# Battery_Charger.net
KiCad netlist of a schematic drawn in Altium Designer
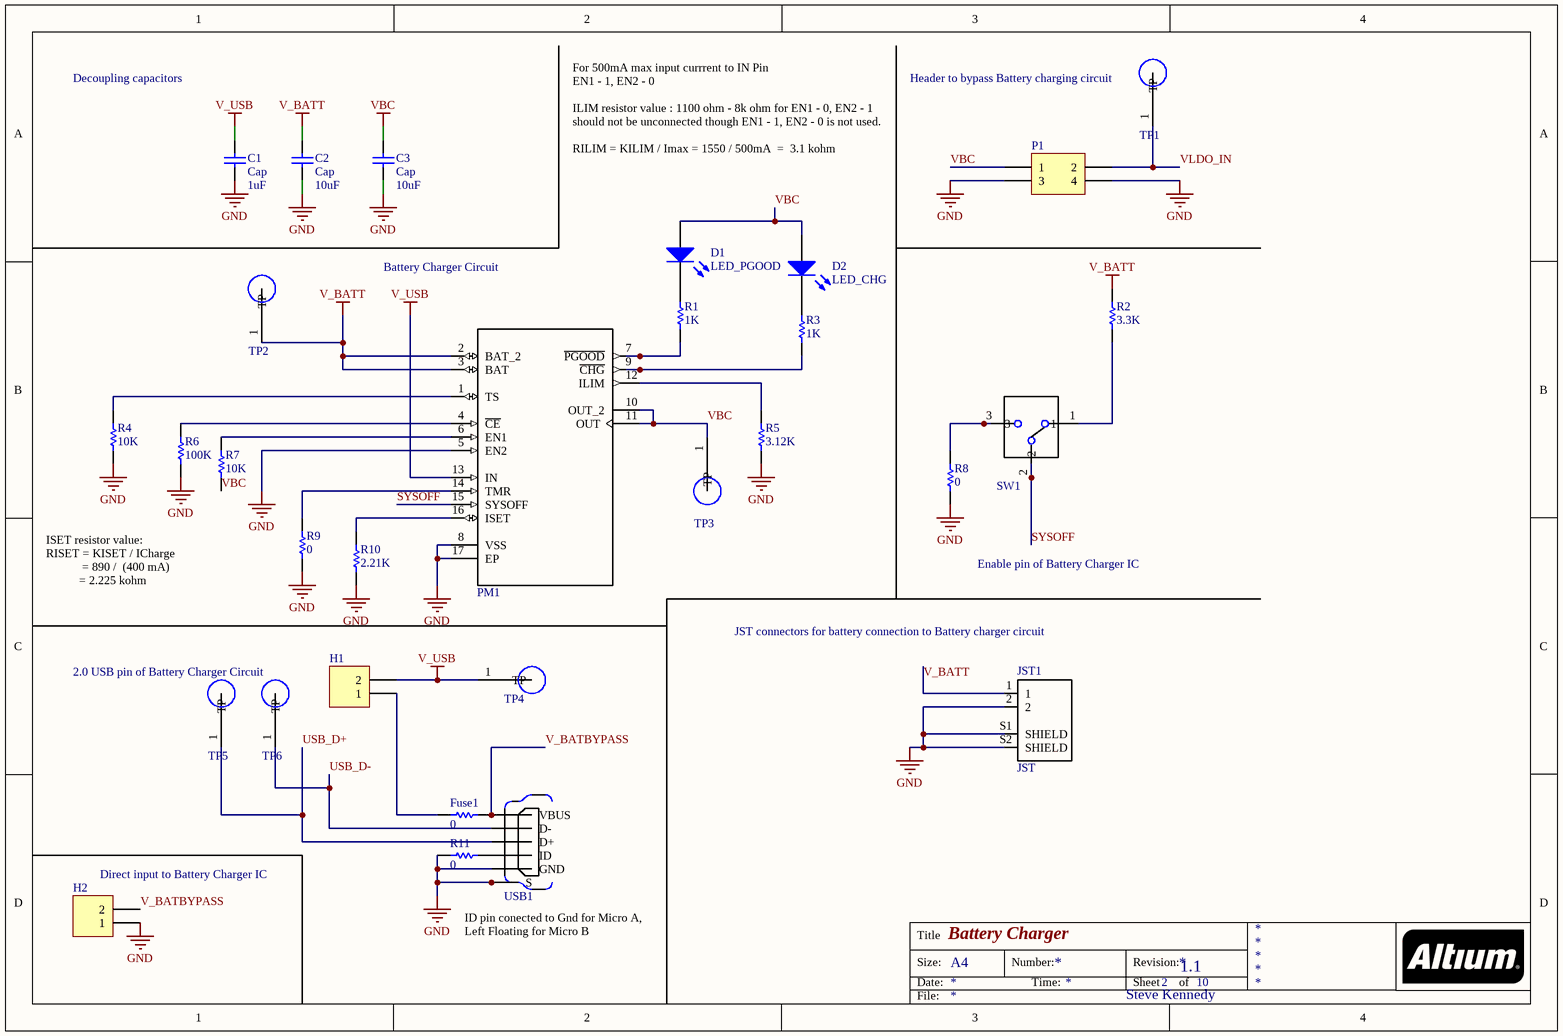
[diagram p0: Battery_Charger.SchDoc]

(export (version "E")
  (design (tool "Eeschema 10.0.6"))
  (components
    (comp (ref "C1")
      (value "Cap")
      (footprint "1608[0603]")
      (description "10000pF ±10% 50V Ceramic Capacitor X7R 0603 (1608 Metric)")
      (fields
        (field (name "ALTIUM_VALUE") "1uF")
        (field (name "DIGI-KEY PART NUMBER") "1276-1009-1-ND")
        (field (name "MANUFACTURER") "Samsung Electro-Mechanics")
      )
      (libsource (lib "Miscellaneous Devices") (part "Cap"))
    )
    (comp (ref "C2")
      (value "Cap")
      (footprint "1608[0603]")
      (description "10000pF ±10% 50V Ceramic Capacitor X7R 0603 (1608 Metric)")
      (fields
        (field (name "ALTIUM_VALUE") "10uF")
        (field (name "DIGI-KEY PART NUMBER") "1276-1009-1-ND")
        (field (name "MANUFACTURER") "Samsung Electro-Mechanics")
      )
      (libsource (lib "Miscellaneous Devices") (part "Cap"))
    )
    (comp (ref "C3")
      (value "Cap")
      (footprint "1608[0603]")
      (description "10000pF ±10% 50V Ceramic Capacitor X7R 0603 (1608 Metric)")
      (fields
        (field (name "ALTIUM_VALUE") "10uF")
        (field (name "DIGI-KEY PART NUMBER") "1276-1009-1-ND")
        (field (name "MANUFACTURER") "Samsung Electro-Mechanics")
      )
      (libsource (lib "Miscellaneous Devices") (part "Cap"))
    )
    (comp (ref "D1")
      (value "LED_PGOOD")
      (footprint "1608[0603]")
      (description "LED GREEN DIFFUSED 0603 SMD")
      (fields
        (field (name "DIGI-KEY PART NUMBER") "475-3118-1-ND")
        (field (name "MANUFACTURER") "OSRAM Opto Semiconductors Inc.")
      )
      (libsource (lib "Miscellaneous Devices") (part "LED2"))
    )
    (comp (ref "D2")
      (value "LED_CHG")
      (footprint "1608[0603]")
      (description "Blue 470nm LED Indication - Discrete 2.85V 0603 (1608 Metric)")
      (fields
        (field (name "DIGI-KEY PART NUMBER") "475-2816-1-ND")
        (field (name "MANUFACTURER") "OSRAM Opto Semiconductors Inc.")
      )
      (libsource (lib "Miscellaneous Devices") (part "LED2"))
    )
    (comp (ref "Fuse1")
      (value "0")
      (footprint "1608[0603]")
      (fields
        (field (name "DIGI-KEY PART NUMBER") "RNCP0603FTD10K0CT-ND")
        (field (name "MANUFACTURER") "Stackpole Electronics Inc")
        (field (name "MANUFACTURER PART NUMBER") "RNCP0603FTD10K0")
      )
      (libsource (lib "Miscellaneous Devices") (part "Res1"))
    )
    (comp (ref "H1")
      (value "Header 2")
      (footprint "HDR1X2")
      (description "CONN HEADER VERT 8POS 2.54MM")
      (fields
        (field (name "DIGI-KEY PART NUMBER") "A121467-ND")
        (field (name "MANUFACTURER") "TE Connectivity AMP Connectors")
      )
      (libsource (lib "Miscellaneous Connectors") (part "Header 2"))
    )
    (comp (ref "H2")
      (value "Header 2")
      (footprint "HDR1X2")
      (description "CONN HEADER VERT 8POS 2.54MM")
      (fields
        (field (name "DIGI-KEY PART NUMBER") "A121467-ND")
        (field (name "MANUFACTURER") "TE Connectivity AMP Connectors")
      )
      (libsource (lib "Miscellaneous Connectors") (part "Header 2"))
    )
    (comp (ref "JST1")
      (value "JST")
      (footprint "JST")
      (description "SWITCH SLIDE SPDT 200MA 12V")
      (fields
        (field (name "DIGI-KEY PART NUMBER") "563-1318-1-ND")
        (field (name "MANUFACTURER") "Nidec Copal Electronics")
      )
      (libsource (lib "JST_header") (part "JST"))
    )
    (comp (ref "P1")
      (value "Header 2X2H")
      (footprint "HDR2X2H")
      (description "CONN HEADER VERT 8POS 2.54MM")
      (fields
        (field (name "DIGI-KEY PART NUMBER") "A121467-ND")
        (field (name "MANUFACTURER") "TE Connectivity AMP Connectors")
      )
      (libsource (lib "Miscellaneous Connectors") (part "Header 2X2H"))
    )
    (comp (ref "PM1")
      (value "POWER_IC")
      (footprint "Power_management")
      (description "IC LI-ION CHARGE MGMT 16-QFN")
      (fields
        (field (name "MANUFACTURER") "Texas Instruments")
        (field (name "DIGI-KEY PART NUMBER") "296-38874-1-ND")
      )
      (libsource (lib "Power_management_chip") (part "POWER_IC"))
    )
    (comp (ref "R1")
      (value "1K")
      (footprint "1608[0603]")
      (fields
        (field (name "DIGI-KEY PART NUMBER") "RNCP0603FTD10K0CT-ND")
        (field (name "MANUFACTURER") "Stackpole Electronics Inc")
        (field (name "MANUFACTURER PART NUMBER") "RNCP0603FTD10K0")
      )
      (libsource (lib "Miscellaneous Devices") (part "Res1"))
    )
    (comp (ref "R2")
      (value "3.3K")
      (footprint "1608[0603]")
      (fields
        (field (name "DIGI-KEY PART NUMBER") "RNCP0603FTD10K0CT-ND")
        (field (name "MANUFACTURER") "Stackpole Electronics Inc")
        (field (name "MANUFACTURER PART NUMBER") "RNCP0603FTD10K0")
      )
      (libsource (lib "Miscellaneous Devices") (part "Res1"))
    )
    (comp (ref "R3")
      (value "1K")
      (footprint "1608[0603]")
      (fields
        (field (name "DIGI-KEY PART NUMBER") "RNCP0603FTD10K0CT-ND")
        (field (name "MANUFACTURER") "Stackpole Electronics Inc")
        (field (name "MANUFACTURER PART NUMBER") "RNCP0603FTD10K0")
      )
      (libsource (lib "Miscellaneous Devices") (part "Res1"))
    )
    (comp (ref "R4")
      (value "10K")
      (footprint "1608[0603]")
      (fields
        (field (name "DIGI-KEY PART NUMBER") "RNCP0603FTD10K0CT-ND")
        (field (name "MANUFACTURER") "Stackpole Electronics Inc")
        (field (name "MANUFACTURER PART NUMBER") "RNCP0603FTD10K0")
      )
      (libsource (lib "Miscellaneous Devices") (part "Res1"))
    )
    (comp (ref "R5")
      (value "3.12K")
      (footprint "1608[0603]")
      (fields
        (field (name "DIGI-KEY PART NUMBER") "311-2562-1-ND")
        (field (name "MANUFACTURER") "Yageo")
        (field (name "MANUFACTURER PART NUMBER") "RT0603DRE073K12L")
      )
      (libsource (lib "Miscellaneous Devices") (part "Res1"))
    )
    (comp (ref "R6")
      (value "100K")
      (footprint "1608[0603]")
      (fields
        (field (name "DIGI-KEY PART NUMBER") "RNCP0603FTD10K0CT-ND")
        (field (name "MANUFACTURER") "Stackpole Electronics Inc")
        (field (name "MANUFACTURER PART NUMBER") "RNCP0603FTD10K0")
      )
      (libsource (lib "Miscellaneous Devices") (part "Res1"))
    )
    (comp (ref "R7")
      (value "10K")
      (footprint "1608[0603]")
      (fields
        (field (name "DIGI-KEY PART NUMBER") "RNCP0603FTD10K0CT-ND")
        (field (name "MANUFACTURER") "Stackpole Electronics Inc")
        (field (name "MANUFACTURER PART NUMBER") "RNCP0603FTD10K0")
      )
      (libsource (lib "Miscellaneous Devices") (part "Res1"))
    )
    (comp (ref "R8")
      (value "0")
      (footprint "1608[0603]")
      (description "RES SMD 0 OHM JUMPER 1/10W 0603")
      (fields (field (name "DIGI-KEY PART NUMBER") "311-0.0GRCT-ND") (field (name "MANUFACTURER") "Yageo"))
      (libsource (lib "Miscellaneous Devices") (part "Res1"))
    )
    (comp (ref "R9")
      (value "0")
      (footprint "1608[0603]")
      (description "RES SMD 0 OHM JUMPER 1/10W 0603")
      (fields (field (name "DIGI-KEY PART NUMBER") "311-0.0GRCT-ND") (field (name "MANUFACTURER") "Yageo"))
      (libsource (lib "Miscellaneous Devices") (part "Res1"))
    )
    (comp (ref "R10")
      (value "2.21K")
      (footprint "1608[0603]")
      (fields
        (field (name "DIGI-KEY PART NUMBER") "P2.21KHCT-ND")
        (field (name "MANUFACTURER") "Panasonic Electronic Components")
        (field (name "MANUFACTURER PART NUMBER") "ERJ-3EKF2211V")
      )
      (libsource (lib "Miscellaneous Devices") (part "Res1"))
    )
    (comp (ref "R11")
      (value "0")
      (footprint "1608[0603]")
      (description "RES SMD 0 OHM JUMPER 1/10W 0603")
      (fields (field (name "DIGI-KEY PART NUMBER") "311-0.0GRCT-ND") (field (name "MANUFACTURER") "Yageo"))
      (libsource (lib "Miscellaneous Devices") (part "Res1"))
    )
    (comp (ref "SW1")
      (value "SW")
      (footprint "SW")
      (description "SWITCH SLIDE SPDT 200MA 12V")
      (fields
        (field (name "MANUFACTURER") "Nidec Copal Electronics")
        (field (name "DIGI-KEY PART NUMBER") "563-1318-1-ND")
      )
      (libsource (lib "Switch") (part "SW"))
    )
    (comp (ref "TP1")
      (value "TP")
      (footprint "TP")
      (description "PC TEST POINT MINIATURE")
      (fields
        (field (name "MANUFACTURER") "Keystone Electronics")
        (field (name "DIGI-KEY PART NUMBER") "36-5019CT-ND")
      )
      (libsource (lib "TP") (part "TP"))
    )
    (comp (ref "TP2")
      (value "TP")
      (footprint "TP")
      (description "PC TEST POINT MINIATURE")
      (fields
        (field (name "DIGI-KEY PART NUMBER") "36-5019CT-ND")
        (field (name "MANUFACTURER") "Keystone Electronics")
      )
      (libsource (lib "TP") (part "TP"))
    )
    (comp (ref "TP3")
      (value "TP")
      (footprint "TP")
      (description "PC TEST POINT MINIATURE")
      (fields
        (field (name "MANUFACTURER") "Keystone Electronics")
        (field (name "DIGI-KEY PART NUMBER") "36-5019CT-ND")
      )
      (libsource (lib "TP") (part "TP"))
    )
    (comp (ref "TP4")
      (value "TP")
      (footprint "TP")
      (description "PC TEST POINT MINIATURE")
      (fields
        (field (name "MANUFACTURER") "Keystone Electronics")
        (field (name "DIGI-KEY PART NUMBER") "36-5019CT-ND")
      )
      (libsource (lib "TP") (part "TP"))
    )
    (comp (ref "TP5")
      (value "TP")
      (footprint "TP")
      (description "PC TEST POINT MINIATURE")
      (fields
        (field (name "MANUFACTURER") "Keystone Electronics")
        (field (name "DIGI-KEY PART NUMBER") "36-5019CT-ND")
      )
      (libsource (lib "TP") (part "TP"))
    )
    (comp (ref "TP6")
      (value "TP")
      (footprint "TP")
      (description "PC TEST POINT MINIATURE")
      (fields
        (field (name "MANUFACTURER") "Keystone Electronics")
        (field (name "DIGI-KEY PART NUMBER") "36-5019CT-ND")
      )
      (libsource (lib "TP") (part "TP"))
    )
    (comp (ref "USB1")
      (value "USB")
      (footprint "USB")
      (description "CONN RCPT USB2.0 MICRO AB SMD RA")
      (fields
        (field (name "DIGI-KEY PART NUMBER") "609-4053-1-ND")
        (field (name "MANUFACTURER") "Amphenol ICC (FCI)")
      )
      (libsource (lib "Project_Parts") (part "USB"))
    )
  )
  (nets
    (net (code "1") (name "/SYSOFF") (class "Default")
      (node (ref "PM1") (pin "15") (pinfunction "SYSOFF_15") (pintype "input"))
      (node (ref "SW1") (pin "2") (pinfunction "2_2") (pintype "bidirectional"))
    )
    (net (code "2") (name "/USB_D+") (class "Default")
      (node (ref "TP5") (pin "1") (pinfunction "TP_1") (pintype "passive"))
      (node (ref "USB1") (pin "3") (pinfunction "D+_3") (pintype "passive"))
    )
    (net (code "3") (name "/USB_D-") (class "Default")
      (node (ref "TP6") (pin "1") (pinfunction "TP_1") (pintype "passive"))
      (node (ref "USB1") (pin "2") (pinfunction "D-_2") (pintype "passive"))
    )
    (net (code "4") (name "/VLDO_IN") (class "Default")
      (node (ref "P1") (pin "2") (pinfunction "2_2") (pintype "passive"))
      (node (ref "TP1") (pin "1") (pinfunction "TP_1") (pintype "passive"))
    )
    (net (code "5") (name "/V_BATBYPASS") (class "Default")
      (node (ref "Fuse1") (pin "1") (pinfunction "1_1") (pintype "passive"))
      (node (ref "H2") (pin "2") (pinfunction "2_2") (pintype "passive"))
      (node (ref "USB1") (pin "1") (pinfunction "VBUS_1") (pintype "power_in"))
    )
    (net (code "6") (name "GND") (class "Default")
      (node (ref "C1") (pin "1") (pinfunction "1_1") (pintype "passive"))
      (node (ref "C2") (pin "1") (pinfunction "1_1") (pintype "passive"))
      (node (ref "C3") (pin "1") (pinfunction "1_1") (pintype "passive"))
      (node (ref "H2") (pin "1") (pinfunction "1_1") (pintype "passive"))
      (node (ref "JST1") (pin "2") (pinfunction "2_2") (pintype "passive"))
      (node (ref "JST1") (pin "S1") (pinfunction "SHIELD_S1") (pintype "passive"))
      (node (ref "JST1") (pin "S2") (pinfunction "SHIELD_S2") (pintype "passive"))
      (node (ref "P1") (pin "3") (pinfunction "3_3") (pintype "passive"))
      (node (ref "P1") (pin "4") (pinfunction "4_4") (pintype "passive"))
      (node (ref "PM1") (pin "17") (pinfunction "EP_17") (pintype "passive"))
      (node (ref "PM1") (pin "5") (pinfunction "EN2_5") (pintype "input"))
      (node (ref "PM1") (pin "8") (pinfunction "VSS_8") (pintype "passive"))
      (node (ref "R10") (pin "1") (pinfunction "1_1") (pintype "passive"))
      (node (ref "R11") (pin "2") (pinfunction "2_2") (pintype "passive"))
      (node (ref "R4") (pin "1") (pinfunction "1_1") (pintype "passive"))
      (node (ref "R5") (pin "1") (pinfunction "1_1") (pintype "passive"))
      (node (ref "R6") (pin "1") (pinfunction "1_1") (pintype "passive"))
      (node (ref "R8") (pin "1") (pinfunction "1_1") (pintype "passive"))
      (node (ref "R9") (pin "1") (pinfunction "1_1") (pintype "passive"))
      (node (ref "USB1") (pin "5") (pinfunction "GND_5") (pintype "power_in"))
      (node (ref "USB1") (pin "6") (pinfunction "S_6") (pintype "power_in"))
      (node (ref "USB1") (pin "7") (pinfunction "S_7") (pintype "power_in"))
      (node (ref "USB1") (pin "8") (pinfunction "S_8") (pintype "power_in"))
      (node (ref "USB1") (pin "9") (pinfunction "S_9") (pintype "power_in"))
    )
    (net (code "7") (name "Net-(D1-K)") (class "Default")
      (node (ref "D1") (pin "2") (pinfunction "K_2") (pintype "passive"))
      (node (ref "R1") (pin "2") (pinfunction "2_2") (pintype "passive"))
    )
    (net (code "8") (name "Net-(D2-K)") (class "Default")
      (node (ref "D2") (pin "2") (pinfunction "K_2") (pintype "passive"))
      (node (ref "R3") (pin "2") (pinfunction "2_2") (pintype "passive"))
    )
    (net (code "9") (name "Net-(Fuse1-Pad2)") (class "Default")
      (node (ref "Fuse1") (pin "2") (pinfunction "2_2") (pintype "passive"))
      (node (ref "H1") (pin "1") (pinfunction "1_1") (pintype "passive"))
    )
    (net (code "10") (name "Net-(PM1-EN1)") (class "Default")
      (node (ref "PM1") (pin "6") (pinfunction "EN1_6") (pintype "input"))
      (node (ref "R7") (pin "2") (pinfunction "2_2") (pintype "passive"))
    )
    (net (code "11") (name "Net-(PM1-ILIM)") (class "Default")
      (node (ref "PM1") (pin "12") (pinfunction "ILIM_12") (pintype "output"))
      (node (ref "R5") (pin "2") (pinfunction "2_2") (pintype "passive"))
    )
    (net (code "12") (name "Net-(PM1-ISET)") (class "Default")
      (node (ref "PM1") (pin "16") (pinfunction "ISET_16") (pintype "bidirectional"))
      (node (ref "R10") (pin "2") (pinfunction "2_2") (pintype "passive"))
    )
    (net (code "13") (name "Net-(PM1-TMR)") (class "Default")
      (node (ref "PM1") (pin "14") (pinfunction "TMR_14") (pintype "input"))
      (node (ref "R9") (pin "2") (pinfunction "2_2") (pintype "passive"))
    )
    (net (code "14") (name "Net-(PM1-TS)") (class "Default")
      (node (ref "PM1") (pin "1") (pinfunction "TS_1") (pintype "bidirectional"))
      (node (ref "R4") (pin "2") (pinfunction "2_2") (pintype "passive"))
    )
    (net (code "15") (name "Net-(PM1-~{CE})") (class "Default")
      (node (ref "PM1") (pin "4") (pinfunction "~{CE}_4") (pintype "input"))
      (node (ref "R6") (pin "2") (pinfunction "2_2") (pintype "passive"))
    )
    (net (code "16") (name "Net-(PM1-~{CHG})") (class "Default")
      (node (ref "PM1") (pin "9") (pinfunction "~{CHG}_9") (pintype "output"))
      (node (ref "R3") (pin "1") (pinfunction "1_1") (pintype "passive"))
    )
    (net (code "17") (name "Net-(PM1-~{PGOOD})") (class "Default")
      (node (ref "PM1") (pin "7") (pinfunction "~{PGOOD}_7") (pintype "output"))
      (node (ref "R1") (pin "1") (pinfunction "1_1") (pintype "passive"))
    )
    (net (code "18") (name "Net-(R2-Pad1)") (class "Default")
      (node (ref "R2") (pin "1") (pinfunction "1_1") (pintype "passive"))
      (node (ref "SW1") (pin "1") (pinfunction "1_1") (pintype "bidirectional"))
    )
    (net (code "19") (name "Net-(R8-Pad2)") (class "Default")
      (node (ref "R8") (pin "2") (pinfunction "2_2") (pintype "passive"))
      (node (ref "SW1") (pin "3") (pinfunction "3_3") (pintype "bidirectional"))
    )
    (net (code "20") (name "Net-(USB1-ID)") (class "Default")
      (node (ref "R11") (pin "1") (pinfunction "1_1") (pintype "passive"))
      (node (ref "USB1") (pin "4") (pinfunction "ID_4") (pintype "passive"))
    )
    (net (code "21") (name "VBC") (class "Default")
      (node (ref "C3") (pin "2") (pinfunction "2_2") (pintype "passive"))
      (node (ref "D1") (pin "1") (pinfunction "A_1") (pintype "passive"))
      (node (ref "D2") (pin "1") (pinfunction "A_1") (pintype "passive"))
      (node (ref "P1") (pin "1") (pinfunction "1_1") (pintype "passive"))
      (node (ref "PM1") (pin "10") (pinfunction "OUT_2_10") (pintype "power_in"))
      (node (ref "PM1") (pin "11") (pinfunction "OUT_11") (pintype "power_in"))
      (node (ref "R7") (pin "1") (pinfunction "1_1") (pintype "passive"))
      (node (ref "TP3") (pin "1") (pinfunction "TP_1") (pintype "passive"))
    )
    (net (code "22") (name "V_BATT") (class "Default")
      (node (ref "C2") (pin "2") (pinfunction "2_2") (pintype "passive"))
      (node (ref "JST1") (pin "1") (pinfunction "1_1") (pintype "passive"))
      (node (ref "PM1") (pin "2") (pinfunction "BAT_2_2") (pintype "bidirectional"))
      (node (ref "PM1") (pin "3") (pinfunction "BAT_3") (pintype "bidirectional"))
      (node (ref "R2") (pin "2") (pinfunction "2_2") (pintype "passive"))
      (node (ref "TP2") (pin "1") (pinfunction "TP_1") (pintype "passive"))
    )
    (net (code "23") (name "V_USB") (class "Default")
      (node (ref "C1") (pin "2") (pinfunction "2_2") (pintype "passive"))
      (node (ref "H1") (pin "2") (pinfunction "2_2") (pintype "passive"))
      (node (ref "PM1") (pin "13") (pinfunction "IN_13") (pintype "input"))
      (node (ref "TP4") (pin "1") (pinfunction "TP_1") (pintype "passive"))
    )
  )
)
